# stm32dev.net
KiCad netlist of a schematic drawn in Altium Designer
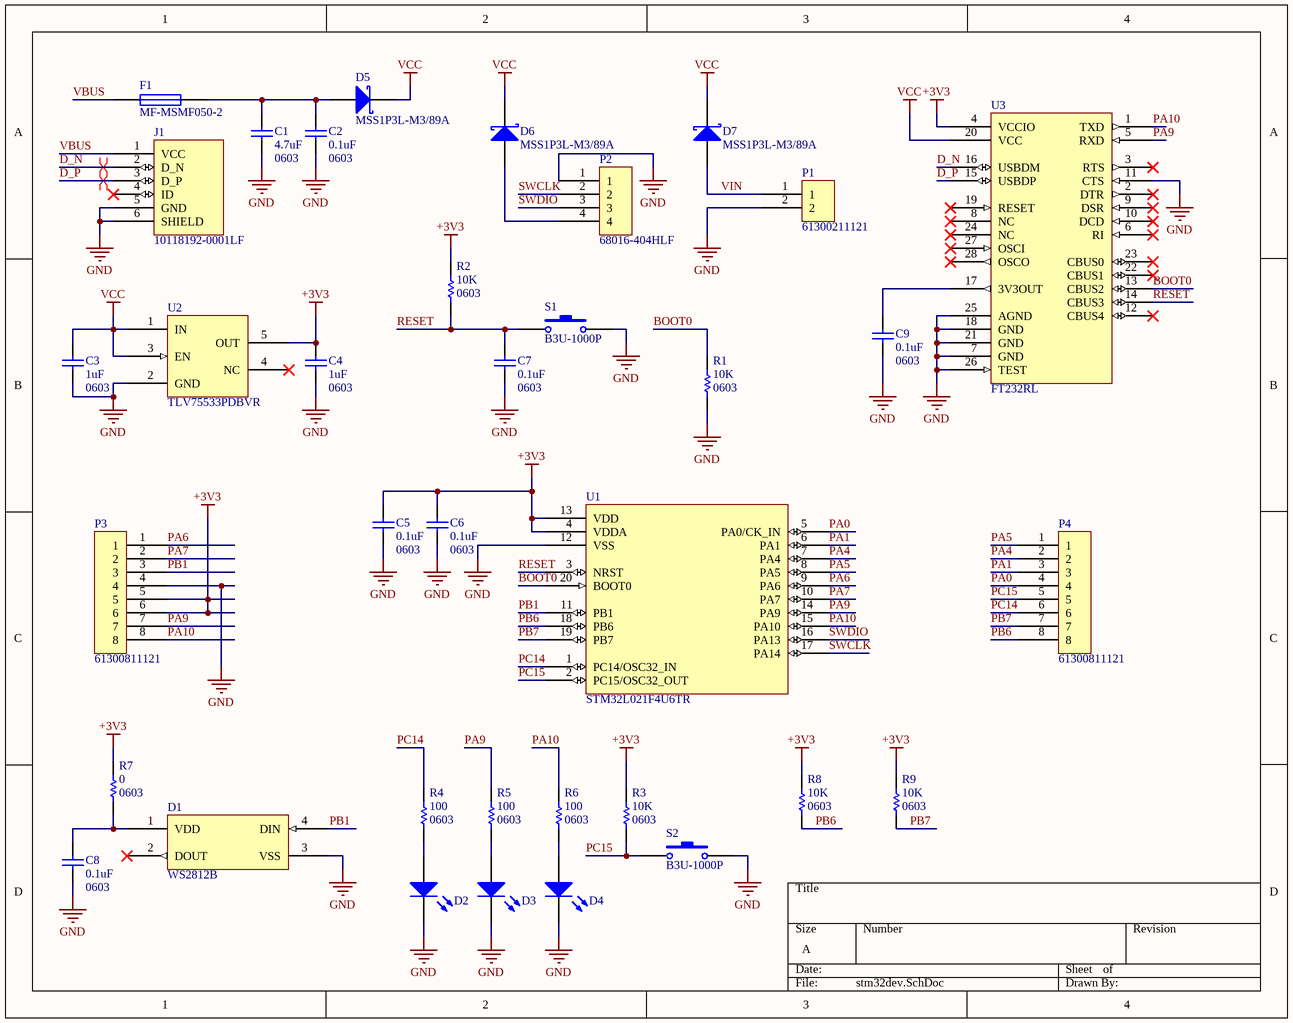
[diagram p0: stm32dev.SchDoc]

(export (version "E")
  (design (tool "Eeschema 10.0.6"))
  (components
    (comp (ref "C1")
      (value "4.7uF")
      (footprint "CAPC1608X09N")
      (description "General purpose capacitor")
      (fields (field (name "PACKAGE") "0603") (field (name "Comment") "Capacitor"))
      (libsource (lib "Schematic_Generic") (part "Capacitor"))
    )
    (comp (ref "C2")
      (value "0.1uF")
      (footprint "CAPC1608X09N")
      (description "General purpose capacitor")
      (fields (field (name "PACKAGE") "0603") (field (name "Comment") "Capacitor"))
      (libsource (lib "Schematic_Generic") (part "Capacitor"))
    )
    (comp (ref "C3")
      (value "1uF")
      (footprint "CAPC1608X09N")
      (description "General purpose capacitor")
      (fields (field (name "PACKAGE") "0603") (field (name "Comment") "Capacitor"))
      (libsource (lib "Schematic_Generic") (part "Capacitor"))
    )
    (comp (ref "C4")
      (value "1uF")
      (footprint "CAPC1608X09N")
      (description "General purpose capacitor")
      (fields (field (name "PACKAGE") "0603") (field (name "Comment") "Capacitor"))
      (libsource (lib "Schematic_Generic") (part "Capacitor"))
    )
    (comp (ref "C5")
      (value "0.1uF")
      (footprint "CAPC1608X09N")
      (description "General purpose capacitor")
      (fields (field (name "PACKAGE") "0603") (field (name "Comment") "Capacitor"))
      (libsource (lib "Schematic_Generic") (part "Capacitor"))
    )
    (comp (ref "C6")
      (value "0.1uF")
      (footprint "CAPC1608X09N")
      (description "General purpose capacitor")
      (fields (field (name "PACKAGE") "0603") (field (name "Comment") "Capacitor"))
      (libsource (lib "Schematic_Generic") (part "Capacitor"))
    )
    (comp (ref "C7")
      (value "0.1uF")
      (footprint "CAPC1608X09N")
      (description "General purpose capacitor")
      (fields (field (name "PACKAGE") "0603") (field (name "Comment") "Capacitor"))
      (libsource (lib "Schematic_Generic") (part "Capacitor"))
    )
    (comp (ref "C8")
      (value "0.1uF")
      (footprint "CAPC1608X09N")
      (description "General purpose capacitor")
      (fields (field (name "PACKAGE") "0603") (field (name "Comment") "Capacitor"))
      (libsource (lib "Schematic_Generic") (part "Capacitor"))
    )
    (comp (ref "C9")
      (value "0.1uF")
      (footprint "CAPC1608X09N")
      (description "General purpose capacitor")
      (fields (field (name "PACKAGE") "0603") (field (name "Comment") "Capacitor"))
      (libsource (lib "Schematic_Generic") (part "Capacitor"))
    )
    (comp (ref "D1")
      (value "WS2812B")
      (footprint "5050")
      (description "NeoPixel 5050 RGB LED with Integrated Driver Chip")
      (fields
        (field (name "MANUFACTURER") "Adafruit Industries")
        (field (name "MANUFACTURER PART NUMBER") "1655")
      )
      (libsource (lib "Schematic_LED") (part "WS2812B"))
    )
    (comp (ref "D2")
      (value "LED")
      (footprint "DIOC1608X09N")
      (description "General purpose LED")
      (libsource (lib "Schematic_Generic") (part "LED"))
    )
    (comp (ref "D3")
      (value "LED")
      (footprint "DIOC1608X09N")
      (description "General purpose LED")
      (libsource (lib "Schematic_Generic") (part "LED"))
    )
    (comp (ref "D4")
      (value "LED")
      (footprint "DIOC1608X09N")
      (description "General purpose LED")
      (libsource (lib "Schematic_Generic") (part "LED"))
    )
    (comp (ref "D5")
      (value "MSS1P3L-M3/89A")
      (footprint "DO-219AD")
      (description "DIODE SCHOTTKY 30V 1A MICROSMP")
      (fields (field (name "MANUFACTURER") "Vishay Semiconductors"))
      (libsource (lib "Schematic_Diode") (part "MSS1P3L-M3/89A"))
    )
    (comp (ref "D6")
      (value "MSS1P3L-M3/89A")
      (footprint "DO-219AD")
      (description "DIODE SCHOTTKY 30V 1A MICROSMP")
      (fields (field (name "MANUFACTURER") "Vishay Semiconductors"))
      (libsource (lib "Schematic_Diode") (part "MSS1P3L-M3/89A"))
    )
    (comp (ref "D7")
      (value "MSS1P3L-M3/89A")
      (footprint "DO-219AD")
      (description "DIODE SCHOTTKY 30V 1A MICROSMP")
      (fields (field (name "MANUFACTURER") "Vishay Semiconductors"))
      (libsource (lib "Schematic_Diode") (part "MSS1P3L-M3/89A"))
    )
    (comp (ref "F1")
      (value "MF-MSMF050-2")
      (footprint "1812 (4532 Metric)")
      (description "PTC Resettable Fuse 100A 15V T/R")
      (fields (field (name "MANUFACTURER") "Bourns"))
      (libsource (lib "Schematic_Fuse") (part "MF-MSMF050-2"))
    )
    (comp (ref "J1")
      (value "10118192-0001LF")
      (footprint "10118192-0001LF")
      (description "Conn Micro USB 2.0 Type B RCP 5 POS 0.65mm Solder RA SMD 5 Terminal 1 Port T/R")
      (fields (field (name "MANUFACTURER") "Framatome Connectors"))
      (libsource (lib "Schematic_Connector") (part "10118192-0001LF"))
    )
    (comp (ref "P1")
      (value "61300211121")
      (footprint "2X1 MALE HEADER")
      (description "Headers & Wire Housings WR-PHD 2.54mm 2Pin THT Header")
      (fields (field (name "MANUFACTURER") "Wurth Electronics"))
      (libsource (lib "Schematic_Connector") (part "61300211121"))
    )
    (comp (ref "P2")
      (value "68016-404HLF")
      (footprint "68016-404HLF")
      (description "CONN HEADER 4POS .100 R/A TIN")
      (fields (field (name "MANUFACTURER") "Amphenol FCI"))
      (libsource (lib "Schematic_Connector") (part "68016-404HLF"))
    )
    (comp (ref "P3")
      (value "61300811121")
      (footprint "8X1 MALE HEADER")
      (fields (field (name "MANUFACTURER") "Wurth Electronics"))
      (libsource (lib "") (part "61300811121_1"))
    )
    (comp (ref "P4")
      (value "61300811121")
      (footprint "8X1 MALE HEADER")
      (fields (field (name "MANUFACTURER") "Wurth Electronics"))
      (libsource (lib "Schematic_Connector") (part "61300811121"))
    )
    (comp (ref "R1")
      (value "10K")
      (footprint "RESC1608X06N")
      (description "General purpose resistor")
      (fields (field (name "PACKAGE") "0603") (field (name "Comment") "Resistor"))
      (libsource (lib "Schematic_Generic") (part "Resistor"))
    )
    (comp (ref "R2")
      (value "10K")
      (footprint "RESC1608X06N")
      (description "General purpose resistor")
      (fields (field (name "PACKAGE") "0603") (field (name "Comment") "Resistor"))
      (libsource (lib "Schematic_Generic") (part "Resistor"))
    )
    (comp (ref "R3")
      (value "10K")
      (footprint "RESC1608X06N")
      (description "General purpose resistor")
      (fields (field (name "PACKAGE") "0603") (field (name "Comment") "Resistor"))
      (libsource (lib "Schematic_Generic") (part "Resistor"))
    )
    (comp (ref "R4")
      (value "100")
      (footprint "RESC1608X06N")
      (description "General purpose resistor")
      (fields (field (name "PACKAGE") "0603") (field (name "Comment") "Resistor"))
      (libsource (lib "Schematic_Generic") (part "Resistor"))
    )
    (comp (ref "R5")
      (value "100")
      (footprint "RESC1608X06N")
      (description "General purpose resistor")
      (fields (field (name "PACKAGE") "0603") (field (name "Comment") "Resistor"))
      (libsource (lib "Schematic_Generic") (part "Resistor"))
    )
    (comp (ref "R6")
      (value "100")
      (footprint "RESC1608X06N")
      (description "General purpose resistor")
      (fields (field (name "PACKAGE") "0603") (field (name "Comment") "Resistor"))
      (libsource (lib "Schematic_Generic") (part "Resistor"))
    )
    (comp (ref "R7")
      (value "0")
      (footprint "RESC1608X06N")
      (description "General purpose resistor")
      (fields (field (name "PACKAGE") "0603") (field (name "Comment") "Resistor"))
      (libsource (lib "Schematic_Generic") (part "Resistor"))
    )
    (comp (ref "R8")
      (value "10K")
      (footprint "RESC1608X06N")
      (description "General purpose resistor")
      (fields (field (name "PACKAGE") "0603") (field (name "Comment") "Resistor"))
      (libsource (lib "Schematic_Generic") (part "Resistor"))
    )
    (comp (ref "R9")
      (value "10K")
      (footprint "RESC1608X06N")
      (description "General purpose resistor")
      (fields (field (name "PACKAGE") "0603") (field (name "Comment") "Resistor"))
      (libsource (lib "Schematic_Generic") (part "Resistor"))
    )
    (comp (ref "S1")
      (value "B3U-1000P")
      (footprint "B3U-1000P")
      (description "OMRON ELECTRONIC COMPONENTS         B3U-1000P            SWITCH, SPST-NO, 0.05A, 12V, SMD")
      (fields (field (name "MANUFACTURER") "Omron"))
      (libsource (lib "Schematic_Button") (part "B3U-1000P"))
    )
    (comp (ref "S2")
      (value "B3U-1000P")
      (footprint "B3U-1000P")
      (description "OMRON ELECTRONIC COMPONENTS         B3U-1000P            SWITCH, SPST-NO, 0.05A, 12V, SMD")
      (fields (field (name "MANUFACTURER") "Omron"))
      (libsource (lib "Schematic_Button") (part "B3U-1000P"))
    )
    (comp (ref "U1")
      (value "STM32L021F4U6TR")
      (footprint "QFN50P300X300X60-20N")
      (description "MCU 32-Bit STM32L021x4 ARM Cortex M0+ RISC 16KB Flash 2.5V/3.3V 20-Pin UFQFPN T/R")
      (fields (field (name "MANUFACTURER") "STMicroelectronics"))
      (libsource (lib "Schematic_MCU") (part "STM32L021F4U6TR"))
    )
    (comp (ref "U2")
      (value "TLV75533PDBVR")
      (footprint "SOT95P280X145-5N")
      (description "IC REG LINEAR 3.3V 500MA SOT23-5")
      (fields (field (name "MANUFACTURER") "Texas Instruments"))
      (libsource (lib "Schematic_PMIC") (part "TLV75533PDBVR"))
    )
    (comp (ref "U3")
      (value "FT232RL")
      (footprint "SOP65P780X200-28N")
      (description "IC USB FS SERIAL UART 28-SSOP")
      (fields (field (name "MANUFACTURER") "FTDI") (field (name "MANUFACTURER PART NUMBER") "FT232RL-REEL"))
      (libsource (lib "Schematic_IC") (part "FT232RL"))
    )
  )
  (nets
    (net (code "1") (name "+3V3") (class "Default")
      (node (ref "C4") (pin "2") (pinfunction "2_2") (pintype "passive"))
      (node (ref "C5") (pin "2") (pinfunction "2_2") (pintype "passive"))
      (node (ref "C6") (pin "2") (pinfunction "2_2") (pintype "passive"))
      (node (ref "P3") (pin "5") (pinfunction "5_5") (pintype "passive"))
      (node (ref "P3") (pin "6") (pinfunction "6_6") (pintype "passive"))
      (node (ref "R2") (pin "2") (pinfunction "2_2") (pintype "passive"))
      (node (ref "R3") (pin "2") (pinfunction "2_2") (pintype "passive"))
      (node (ref "R7") (pin "2") (pinfunction "2_2") (pintype "passive"))
      (node (ref "R8") (pin "2") (pinfunction "2_2") (pintype "passive"))
      (node (ref "R9") (pin "2") (pinfunction "2_2") (pintype "passive"))
      (node (ref "U1") (pin "13") (pinfunction "VDD_13") (pintype "power_in"))
      (node (ref "U1") (pin "4") (pinfunction "VDDA_4") (pintype "power_in"))
      (node (ref "U2") (pin "5") (pinfunction "OUT_5") (pintype "power_in"))
      (node (ref "U3") (pin "4") (pinfunction "VCCIO_4") (pintype "power_in"))
    )
    (net (code "2") (name "/BOOT0") (class "Default")
      (node (ref "R1") (pin "2") (pinfunction "2_2") (pintype "passive"))
      (node (ref "U1") (pin "20") (pinfunction "BOOT0_20") (pintype "input"))
      (node (ref "U3") (pin "13") (pinfunction "CBUS2_13") (pintype "bidirectional"))
    )
    (net (code "3") (name "/D_N") (class "Default")
      (node (ref "J1") (pin "2") (pinfunction "D_N_2") (pintype "bidirectional"))
      (node (ref "U3") (pin "16") (pinfunction "USBDM_16") (pintype "bidirectional"))
    )
    (net (code "4") (name "/D_P") (class "Default")
      (node (ref "J1") (pin "3") (pinfunction "D_P_3") (pintype "bidirectional"))
      (node (ref "U3") (pin "15") (pinfunction "USBDP_15") (pintype "bidirectional"))
    )
    (net (code "5") (name "/PA0") (class "Default")
      (node (ref "P4") (pin "4") (pinfunction "4_4") (pintype "passive"))
      (node (ref "U1") (pin "5") (pinfunction "PA0/CK_IN_5") (pintype "bidirectional"))
    )
    (net (code "6") (name "/PA1") (class "Default")
      (node (ref "P4") (pin "3") (pinfunction "3_3") (pintype "passive"))
      (node (ref "U1") (pin "6") (pinfunction "PA1_6") (pintype "bidirectional"))
    )
    (net (code "7") (name "/PA4") (class "Default")
      (node (ref "P4") (pin "2") (pinfunction "2_2") (pintype "passive"))
      (node (ref "U1") (pin "7") (pinfunction "PA4_7") (pintype "bidirectional"))
    )
    (net (code "8") (name "/PA5") (class "Default")
      (node (ref "P4") (pin "1") (pinfunction "1_1") (pintype "passive"))
      (node (ref "U1") (pin "8") (pinfunction "PA5_8") (pintype "bidirectional"))
    )
    (net (code "9") (name "/PA6") (class "Default")
      (node (ref "P3") (pin "1") (pinfunction "1_1") (pintype "passive"))
      (node (ref "U1") (pin "9") (pinfunction "PA6_9") (pintype "bidirectional"))
    )
    (net (code "10") (name "/PA7") (class "Default")
      (node (ref "P3") (pin "2") (pinfunction "2_2") (pintype "passive"))
      (node (ref "U1") (pin "10") (pinfunction "PA7_10") (pintype "bidirectional"))
    )
    (net (code "11") (name "/PA9") (class "Default")
      (node (ref "P3") (pin "7") (pinfunction "7_7") (pintype "passive"))
      (node (ref "R5") (pin "2") (pinfunction "2_2") (pintype "passive"))
      (node (ref "U1") (pin "14") (pinfunction "PA9_14") (pintype "bidirectional"))
      (node (ref "U3") (pin "5") (pinfunction "RXD_5") (pintype "input"))
    )
    (net (code "12") (name "/PA10") (class "Default")
      (node (ref "P3") (pin "8") (pinfunction "8_8") (pintype "passive"))
      (node (ref "R6") (pin "2") (pinfunction "2_2") (pintype "passive"))
      (node (ref "U1") (pin "15") (pinfunction "PA10_15") (pintype "bidirectional"))
      (node (ref "U3") (pin "1") (pinfunction "TXD_1") (pintype "output"))
    )
    (net (code "13") (name "/PB1") (class "Default")
      (node (ref "D1") (pin "4") (pinfunction "DIN_4") (pintype "input"))
      (node (ref "P3") (pin "3") (pinfunction "3_3") (pintype "passive"))
      (node (ref "U1") (pin "11") (pinfunction "PB1_11") (pintype "bidirectional"))
    )
    (net (code "14") (name "/PB6") (class "Default")
      (node (ref "P4") (pin "8") (pinfunction "8_8") (pintype "passive"))
      (node (ref "R8") (pin "1") (pinfunction "1_1") (pintype "passive"))
      (node (ref "U1") (pin "18") (pinfunction "PB6_18") (pintype "bidirectional"))
    )
    (net (code "15") (name "/PB7") (class "Default")
      (node (ref "P4") (pin "7") (pinfunction "7_7") (pintype "passive"))
      (node (ref "R9") (pin "1") (pinfunction "1_1") (pintype "passive"))
      (node (ref "U1") (pin "19") (pinfunction "PB7_19") (pintype "bidirectional"))
    )
    (net (code "16") (name "/PC14") (class "Default")
      (node (ref "P4") (pin "6") (pinfunction "6_6") (pintype "passive"))
      (node (ref "R4") (pin "2") (pinfunction "2_2") (pintype "passive"))
      (node (ref "U1") (pin "1") (pinfunction "PC14/OSC32_IN_1") (pintype "bidirectional"))
    )
    (net (code "17") (name "/PC15") (class "Default")
      (node (ref "P4") (pin "5") (pinfunction "5_5") (pintype "passive"))
      (node (ref "R3") (pin "1") (pinfunction "1_1") (pintype "passive"))
      (node (ref "S2") (pin "1") (pinfunction "1_1") (pintype "passive"))
      (node (ref "U1") (pin "2") (pinfunction "PC15/OSC32_OUT_2") (pintype "bidirectional"))
    )
    (net (code "18") (name "/RESET") (class "Default")
      (node (ref "C7") (pin "2") (pinfunction "2_2") (pintype "passive"))
      (node (ref "R2") (pin "1") (pinfunction "1_1") (pintype "passive"))
      (node (ref "S1") (pin "1") (pinfunction "1_1") (pintype "passive"))
      (node (ref "U1") (pin "3") (pinfunction "NRST_3") (pintype "bidirectional"))
      (node (ref "U3") (pin "14") (pinfunction "CBUS3_14") (pintype "bidirectional"))
    )
    (net (code "19") (name "/SWCLK") (class "Default")
      (node (ref "P2") (pin "2") (pinfunction "2_2") (pintype "passive"))
      (node (ref "U1") (pin "17") (pinfunction "PA14_17") (pintype "bidirectional"))
    )
    (net (code "20") (name "/SWDIO") (class "Default")
      (node (ref "P2") (pin "3") (pinfunction "3_3") (pintype "passive"))
      (node (ref "U1") (pin "16") (pinfunction "PA13_16") (pintype "bidirectional"))
    )
    (net (code "21") (name "/VBUS") (class "Default")
      (node (ref "F1") (pin "1") (pinfunction "1_1") (pintype "passive"))
      (node (ref "J1") (pin "1") (pinfunction "VCC_1") (pintype "power_in"))
    )
    (net (code "22") (name "/VIN") (class "Default")
      (node (ref "D7") (pin "1") (pinfunction "A_1") (pintype "passive"))
      (node (ref "P1") (pin "1") (pinfunction "1_1") (pintype "passive"))
    )
    (net (code "23") (name "GND") (class "Default")
      (node (ref "C1") (pin "1") (pinfunction "1_1") (pintype "passive"))
      (node (ref "C2") (pin "1") (pinfunction "1_1") (pintype "passive"))
      (node (ref "C3") (pin "1") (pinfunction "1_1") (pintype "passive"))
      (node (ref "C4") (pin "1") (pinfunction "1_1") (pintype "passive"))
      (node (ref "C5") (pin "1") (pinfunction "1_1") (pintype "passive"))
      (node (ref "C6") (pin "1") (pinfunction "1_1") (pintype "passive"))
      (node (ref "C7") (pin "1") (pinfunction "1_1") (pintype "passive"))
      (node (ref "C8") (pin "1") (pinfunction "1_1") (pintype "passive"))
      (node (ref "C9") (pin "1") (pinfunction "1_1") (pintype "passive"))
      (node (ref "D1") (pin "3") (pinfunction "VSS_3") (pintype "power_in"))
      (node (ref "D2") (pin "2") (pinfunction "K_2") (pintype "passive"))
      (node (ref "D3") (pin "2") (pinfunction "K_2") (pintype "passive"))
      (node (ref "D4") (pin "2") (pinfunction "K_2") (pintype "passive"))
      (node (ref "J1") (pin "5") (pinfunction "GND_5") (pintype "power_in"))
      (node (ref "J1") (pin "6") (pinfunction "SHIELD_6") (pintype "passive"))
      (node (ref "P1") (pin "2") (pinfunction "2_2") (pintype "passive"))
      (node (ref "P2") (pin "1") (pinfunction "1_1") (pintype "passive"))
      (node (ref "P3") (pin "4") (pinfunction "4_4") (pintype "passive"))
      (node (ref "R1") (pin "1") (pinfunction "1_1") (pintype "passive"))
      (node (ref "S1") (pin "2") (pinfunction "2_2") (pintype "passive"))
      (node (ref "S2") (pin "2") (pinfunction "2_2") (pintype "passive"))
      (node (ref "U1") (pin "12") (pinfunction "VSS_12") (pintype "power_in"))
      (node (ref "U2") (pin "2") (pinfunction "GND_2") (pintype "power_in"))
      (node (ref "U3") (pin "11") (pinfunction "CTS_11") (pintype "input"))
      (node (ref "U3") (pin "18") (pinfunction "GND_18") (pintype "power_in"))
      (node (ref "U3") (pin "21") (pinfunction "GND_21") (pintype "power_in"))
      (node (ref "U3") (pin "25") (pinfunction "AGND_25") (pintype "power_in"))
      (node (ref "U3") (pin "26") (pinfunction "TEST_26") (pintype "input"))
      (node (ref "U3") (pin "7") (pinfunction "GND_7") (pintype "power_in"))
    )
    (net (code "24") (name "Net-(D1-VDD)") (class "Default")
      (node (ref "C8") (pin "2") (pinfunction "2_2") (pintype "passive"))
      (node (ref "D1") (pin "1") (pinfunction "VDD_1") (pintype "power_in"))
      (node (ref "R7") (pin "1") (pinfunction "1_1") (pintype "passive"))
    )
    (net (code "25") (name "Net-(D2-A)") (class "Default")
      (node (ref "D2") (pin "1") (pinfunction "A_1") (pintype "passive"))
      (node (ref "R4") (pin "1") (pinfunction "1_1") (pintype "passive"))
    )
    (net (code "26") (name "Net-(D3-A)") (class "Default")
      (node (ref "D3") (pin "1") (pinfunction "A_1") (pintype "passive"))
      (node (ref "R5") (pin "1") (pinfunction "1_1") (pintype "passive"))
    )
    (net (code "27") (name "Net-(D4-A)") (class "Default")
      (node (ref "D4") (pin "1") (pinfunction "A_1") (pintype "passive"))
      (node (ref "R6") (pin "1") (pinfunction "1_1") (pintype "passive"))
    )
    (net (code "28") (name "Net-(D5-A)") (class "Default")
      (node (ref "C1") (pin "2") (pinfunction "2_2") (pintype "passive"))
      (node (ref "C2") (pin "2") (pinfunction "2_2") (pintype "passive"))
      (node (ref "D5") (pin "1") (pinfunction "A_1") (pintype "passive"))
      (node (ref "F1") (pin "2") (pinfunction "2_2") (pintype "passive"))
    )
    (net (code "29") (name "Net-(D6-A)") (class "Default")
      (node (ref "D6") (pin "1") (pinfunction "A_1") (pintype "passive"))
      (node (ref "P2") (pin "4") (pinfunction "4_4") (pintype "passive"))
    )
    (net (code "30") (name "Net-(U3-3V3OUT)") (class "Default")
      (node (ref "C9") (pin "2") (pinfunction "2_2") (pintype "passive"))
      (node (ref "U3") (pin "17") (pinfunction "3V3OUT_17") (pintype "output"))
    )
    (net (code "31") (name "VCC") (class "Default")
      (node (ref "C3") (pin "2") (pinfunction "2_2") (pintype "passive"))
      (node (ref "D5") (pin "2") (pinfunction "K_2") (pintype "passive"))
      (node (ref "D6") (pin "2") (pinfunction "K_2") (pintype "passive"))
      (node (ref "D7") (pin "2") (pinfunction "K_2") (pintype "passive"))
      (node (ref "U2") (pin "1") (pinfunction "IN_1") (pintype "power_in"))
      (node (ref "U2") (pin "3") (pinfunction "EN_3") (pintype "input"))
      (node (ref "U3") (pin "20") (pinfunction "VCC_20") (pintype "power_in"))
    )
    (net (code "32") (name "unconnected-(D1-DOUT-Pad2)") (class "Default")
      (node (ref "D1") (pin "2") (pinfunction "DOUT_2") (pintype "output+no_connect"))
    )
    (net (code "33") (name "unconnected-(J1-ID-Pad4)") (class "Default")
      (node (ref "J1") (pin "4") (pinfunction "ID_4") (pintype "bidirectional+no_connect"))
    )
    (net (code "34") (name "unconnected-(U2-NC-Pad4)") (class "Default")
      (node (ref "U2") (pin "4") (pinfunction "NC_4") (pintype "passive+no_connect"))
    )
    (net (code "35") (name "unconnected-(U3-CBUS0-Pad23)") (class "Default")
      (node (ref "U3") (pin "23") (pinfunction "CBUS0_23") (pintype "bidirectional+no_connect"))
    )
    (net (code "36") (name "unconnected-(U3-CBUS1-Pad22)") (class "Default")
      (node (ref "U3") (pin "22") (pinfunction "CBUS1_22") (pintype "bidirectional+no_connect"))
    )
    (net (code "37") (name "unconnected-(U3-CBUS4-Pad12)") (class "Default")
      (node (ref "U3") (pin "12") (pinfunction "CBUS4_12") (pintype "bidirectional+no_connect"))
    )
    (net (code "38") (name "unconnected-(U3-DCD-Pad10)") (class "Default")
      (node (ref "U3") (pin "10") (pinfunction "DCD_10") (pintype "input+no_connect"))
    )
    (net (code "39") (name "unconnected-(U3-DSR-Pad9)") (class "Default")
      (node (ref "U3") (pin "9") (pinfunction "DSR_9") (pintype "input+no_connect"))
    )
    (net (code "40") (name "unconnected-(U3-DTR-Pad2)") (class "Default")
      (node (ref "U3") (pin "2") (pinfunction "DTR_2") (pintype "output+no_connect"))
    )
    (net (code "41") (name "unconnected-(U3-NC-Pad8)") (class "Default")
      (node (ref "U3") (pin "8") (pinfunction "NC_8") (pintype "passive+no_connect"))
    )
    (net (code "42") (name "unconnected-(U3-NC-Pad24)") (class "Default")
      (node (ref "U3") (pin "24") (pinfunction "NC_24") (pintype "passive+no_connect"))
    )
    (net (code "43") (name "unconnected-(U3-OSCI-Pad27)") (class "Default")
      (node (ref "U3") (pin "27") (pinfunction "OSCI_27") (pintype "input+no_connect"))
    )
    (net (code "44") (name "unconnected-(U3-OSCO-Pad28)") (class "Default")
      (node (ref "U3") (pin "28") (pinfunction "OSCO_28") (pintype "output+no_connect"))
    )
    (net (code "45") (name "unconnected-(U3-RESET-Pad19)") (class "Default")
      (node (ref "U3") (pin "19") (pinfunction "RESET_19") (pintype "input+no_connect"))
    )
    (net (code "46") (name "unconnected-(U3-RI-Pad6)") (class "Default")
      (node (ref "U3") (pin "6") (pinfunction "RI_6") (pintype "input+no_connect"))
    )
    (net (code "47") (name "unconnected-(U3-RTS-Pad3)") (class "Default")
      (node (ref "U3") (pin "3") (pinfunction "RTS_3") (pintype "output+no_connect"))
    )
  )
)
